# ECFFL2023-schem.net
KiCad netlist of a schematic drawn in EasyEDA
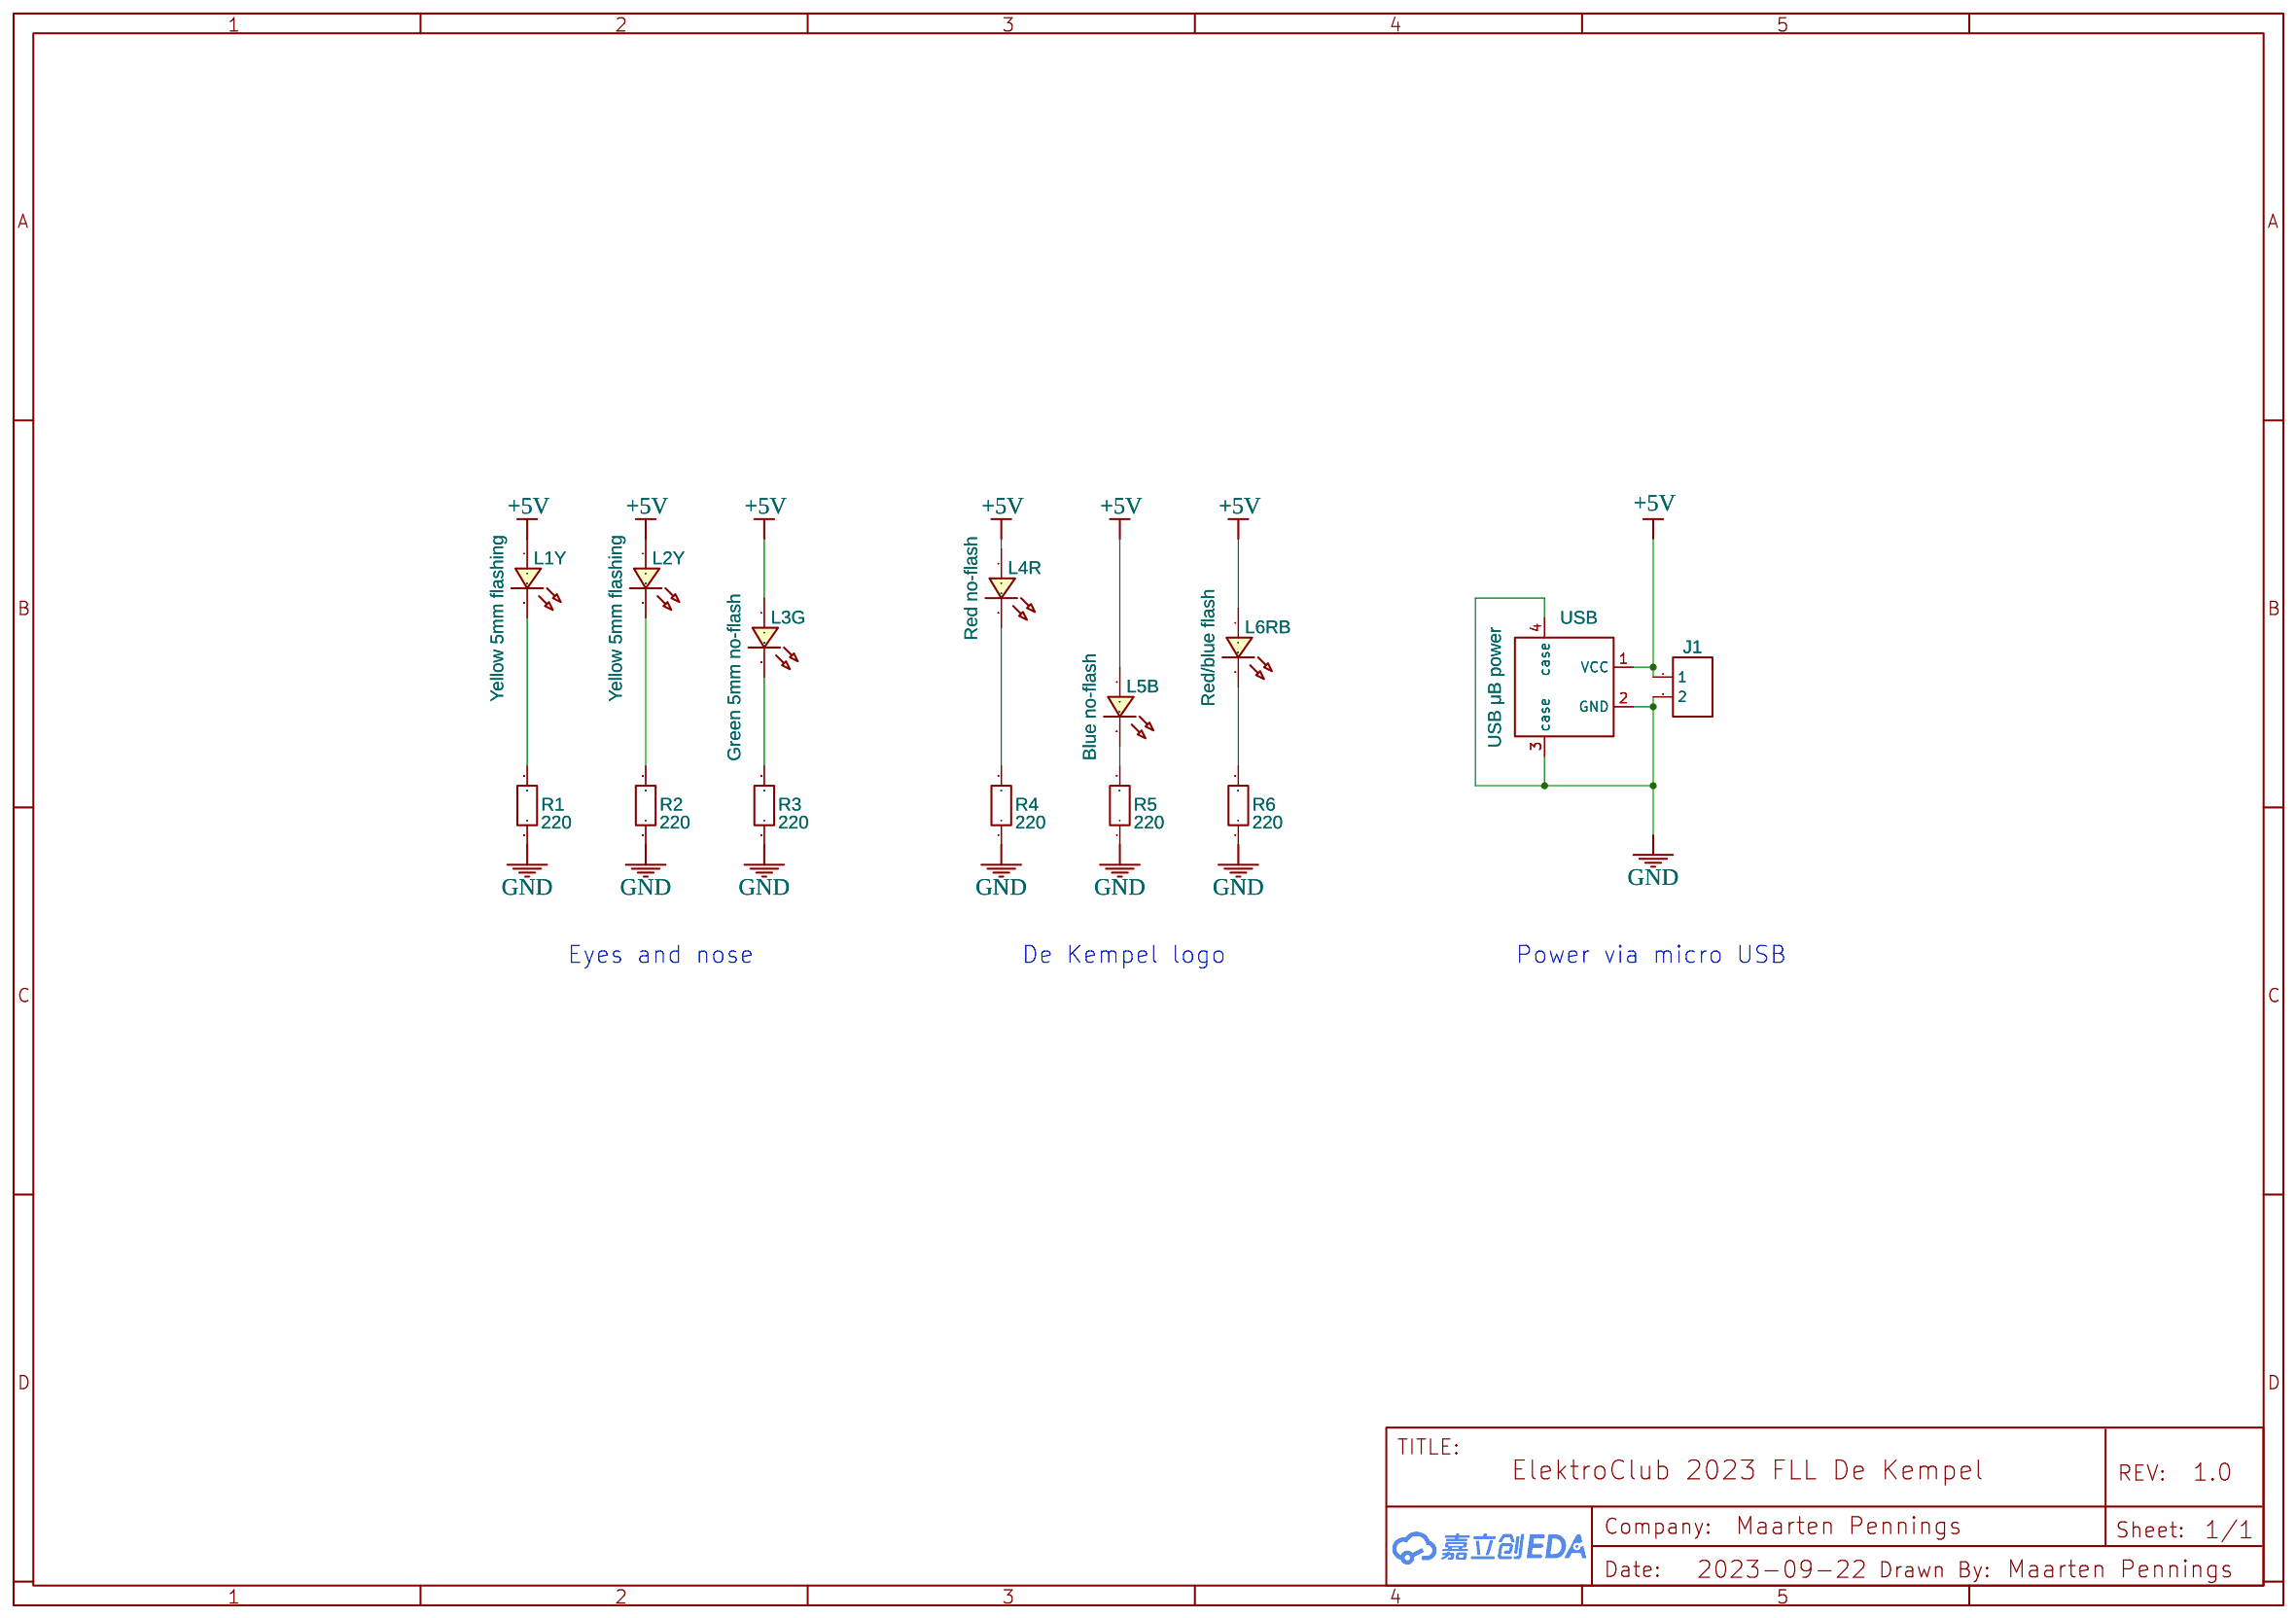
[diagram p0: schematic sheet]

(export (version "E")
  (design (tool "Eeschema 10.0.6"))
  (components
    (comp (ref "J1") (value "HDR-M-2.54_1x2") (libsource (lib "") (part "HDR-M-2.54_1x2")))
    (comp (ref "L1Y")
      (value "Yellow 5mm flashing")
      (fields
        (field (name "Manufacturer Part") "333-2SYGD/S530-E2")
        (field (name "Manufacturer") "EVERLIGHT(台湾亿光)")
      )
      (libsource (lib "") (part "LED-TH-5mm_G"))
    )
    (comp (ref "L2Y")
      (value "Yellow 5mm flashing")
      (fields
        (field (name "Manufacturer Part") "333-2SYGD/S530-E2")
        (field (name "Manufacturer") "EVERLIGHT(台湾亿光)")
      )
      (libsource (lib "") (part "LED-TH-5mm_G_2"))
    )
    (comp (ref "L3G")
      (value "Green 5mm no-flash")
      (fields
        (field (name "Manufacturer Part") "333-2SYGD/S530-E2")
        (field (name "Manufacturer") "EVERLIGHT(台湾亿光)")
      )
      (libsource (lib "") (part "LED-TH-5mm_G_1"))
    )
    (comp (ref "L4R")
      (value "Red no-flash")
      (fields
        (field (name "Manufacturer Part") "333-2SURD/S530-A3")
        (field (name "Manufacturer") "EVERLIGHT(台湾亿光)")
      )
      (libsource (lib "") (part "LED-TH-5mm_R"))
    )
    (comp (ref "L5B") (value "Blue no-flash") (libsource (lib "") (part "LED-TH-5mm_B_1")))
    (comp (ref "L6RB") (value "Red/blue flash") (libsource (lib "") (part "LED-TH-5mm_B")))
    (comp (ref "R1") (value "220") (libsource (lib "") (part "R_AXIAL-0.4_EU")))
    (comp (ref "R2") (value "220") (libsource (lib "") (part "R_AXIAL-0.4_EU")))
    (comp (ref "R3") (value "220") (libsource (lib "") (part "R_AXIAL-0.4_EU")))
    (comp (ref "R4") (value "220") (libsource (lib "") (part "R_AXIAL-0.4_EU")))
    (comp (ref "R5") (value "220") (libsource (lib "") (part "R_AXIAL-0.4_EU")))
    (comp (ref "R6") (value "220") (libsource (lib "") (part "R_AXIAL-0.4_EU")))
    (comp (ref "USB")
      (value "USB μB power")
      (fields (field (name "Manufacturer Part") "JK1-268") (field (name "Manufacturer") "HBXINTAO"))
      (libsource (lib "") (part "USB μB power"))
    )
  )
  (nets
    (net (code "1") (name "+5V") (class "Default")
      (node (ref "J1") (pin "1") (pinfunction "1_1") (pintype "unspecified"))
      (node (ref "L1Y") (pin "1") (pinfunction "1_1") (pintype "unspecified"))
      (node (ref "L2Y") (pin "1") (pinfunction "1_1") (pintype "unspecified"))
      (node (ref "L3G") (pin "1") (pinfunction "1_1") (pintype "unspecified"))
      (node (ref "L4R") (pin "1") (pinfunction "1_1") (pintype "unspecified"))
      (node (ref "L5B") (pin "1") (pinfunction "1_1") (pintype "unspecified"))
      (node (ref "L6RB") (pin "1") (pinfunction "1_1") (pintype "unspecified"))
      (node (ref "USB") (pin "1") (pinfunction "VCC_1") (pintype "unspecified"))
    )
    (net (code "2") (name "GND") (class "Default")
      (node (ref "J1") (pin "2") (pinfunction "2_2") (pintype "unspecified"))
      (node (ref "R1") (pin "1") (pinfunction "1_1") (pintype "unspecified"))
      (node (ref "R2") (pin "1") (pinfunction "1_1") (pintype "unspecified"))
      (node (ref "R3") (pin "1") (pinfunction "1_1") (pintype "unspecified"))
      (node (ref "R4") (pin "1") (pinfunction "1_1") (pintype "unspecified"))
      (node (ref "R5") (pin "1") (pinfunction "1_1") (pintype "unspecified"))
      (node (ref "R6") (pin "1") (pinfunction "1_1") (pintype "unspecified"))
      (node (ref "USB") (pin "2") (pinfunction "GND_2") (pintype "unspecified"))
      (node (ref "USB") (pin "3") (pinfunction "case_3") (pintype "unspecified"))
      (node (ref "USB") (pin "4") (pinfunction "case_4") (pintype "unspecified"))
    )
    (net (code "3") (name "Net-(L1Y-Pad2)") (class "Default")
      (node (ref "L1Y") (pin "2") (pinfunction "2_2") (pintype "unspecified"))
      (node (ref "R1") (pin "2") (pinfunction "2_2") (pintype "unspecified"))
    )
    (net (code "4") (name "Net-(L2Y-Pad2)") (class "Default")
      (node (ref "L2Y") (pin "2") (pinfunction "2_2") (pintype "unspecified"))
      (node (ref "R2") (pin "2") (pinfunction "2_2") (pintype "unspecified"))
    )
    (net (code "5") (name "Net-(L3G-Pad2)") (class "Default")
      (node (ref "L3G") (pin "2") (pinfunction "2_2") (pintype "unspecified"))
      (node (ref "R3") (pin "2") (pinfunction "2_2") (pintype "unspecified"))
    )
    (net (code "6") (name "Net-(L4R-Pad2)") (class "Default")
      (node (ref "L4R") (pin "2") (pinfunction "2_2") (pintype "unspecified"))
      (node (ref "R4") (pin "2") (pinfunction "2_2") (pintype "unspecified"))
    )
    (net (code "7") (name "Net-(L5B-Pad2)") (class "Default")
      (node (ref "L5B") (pin "2") (pinfunction "2_2") (pintype "unspecified"))
      (node (ref "R5") (pin "2") (pinfunction "2_2") (pintype "unspecified"))
    )
    (net (code "8") (name "Net-(L6RB-Pad2)") (class "Default")
      (node (ref "L6RB") (pin "2") (pinfunction "2_2") (pintype "unspecified"))
      (node (ref "R6") (pin "2") (pinfunction "2_2") (pintype "unspecified"))
    )
  )
)
